# 4G.net
KiCad netlist of a schematic drawn in Altium Designer
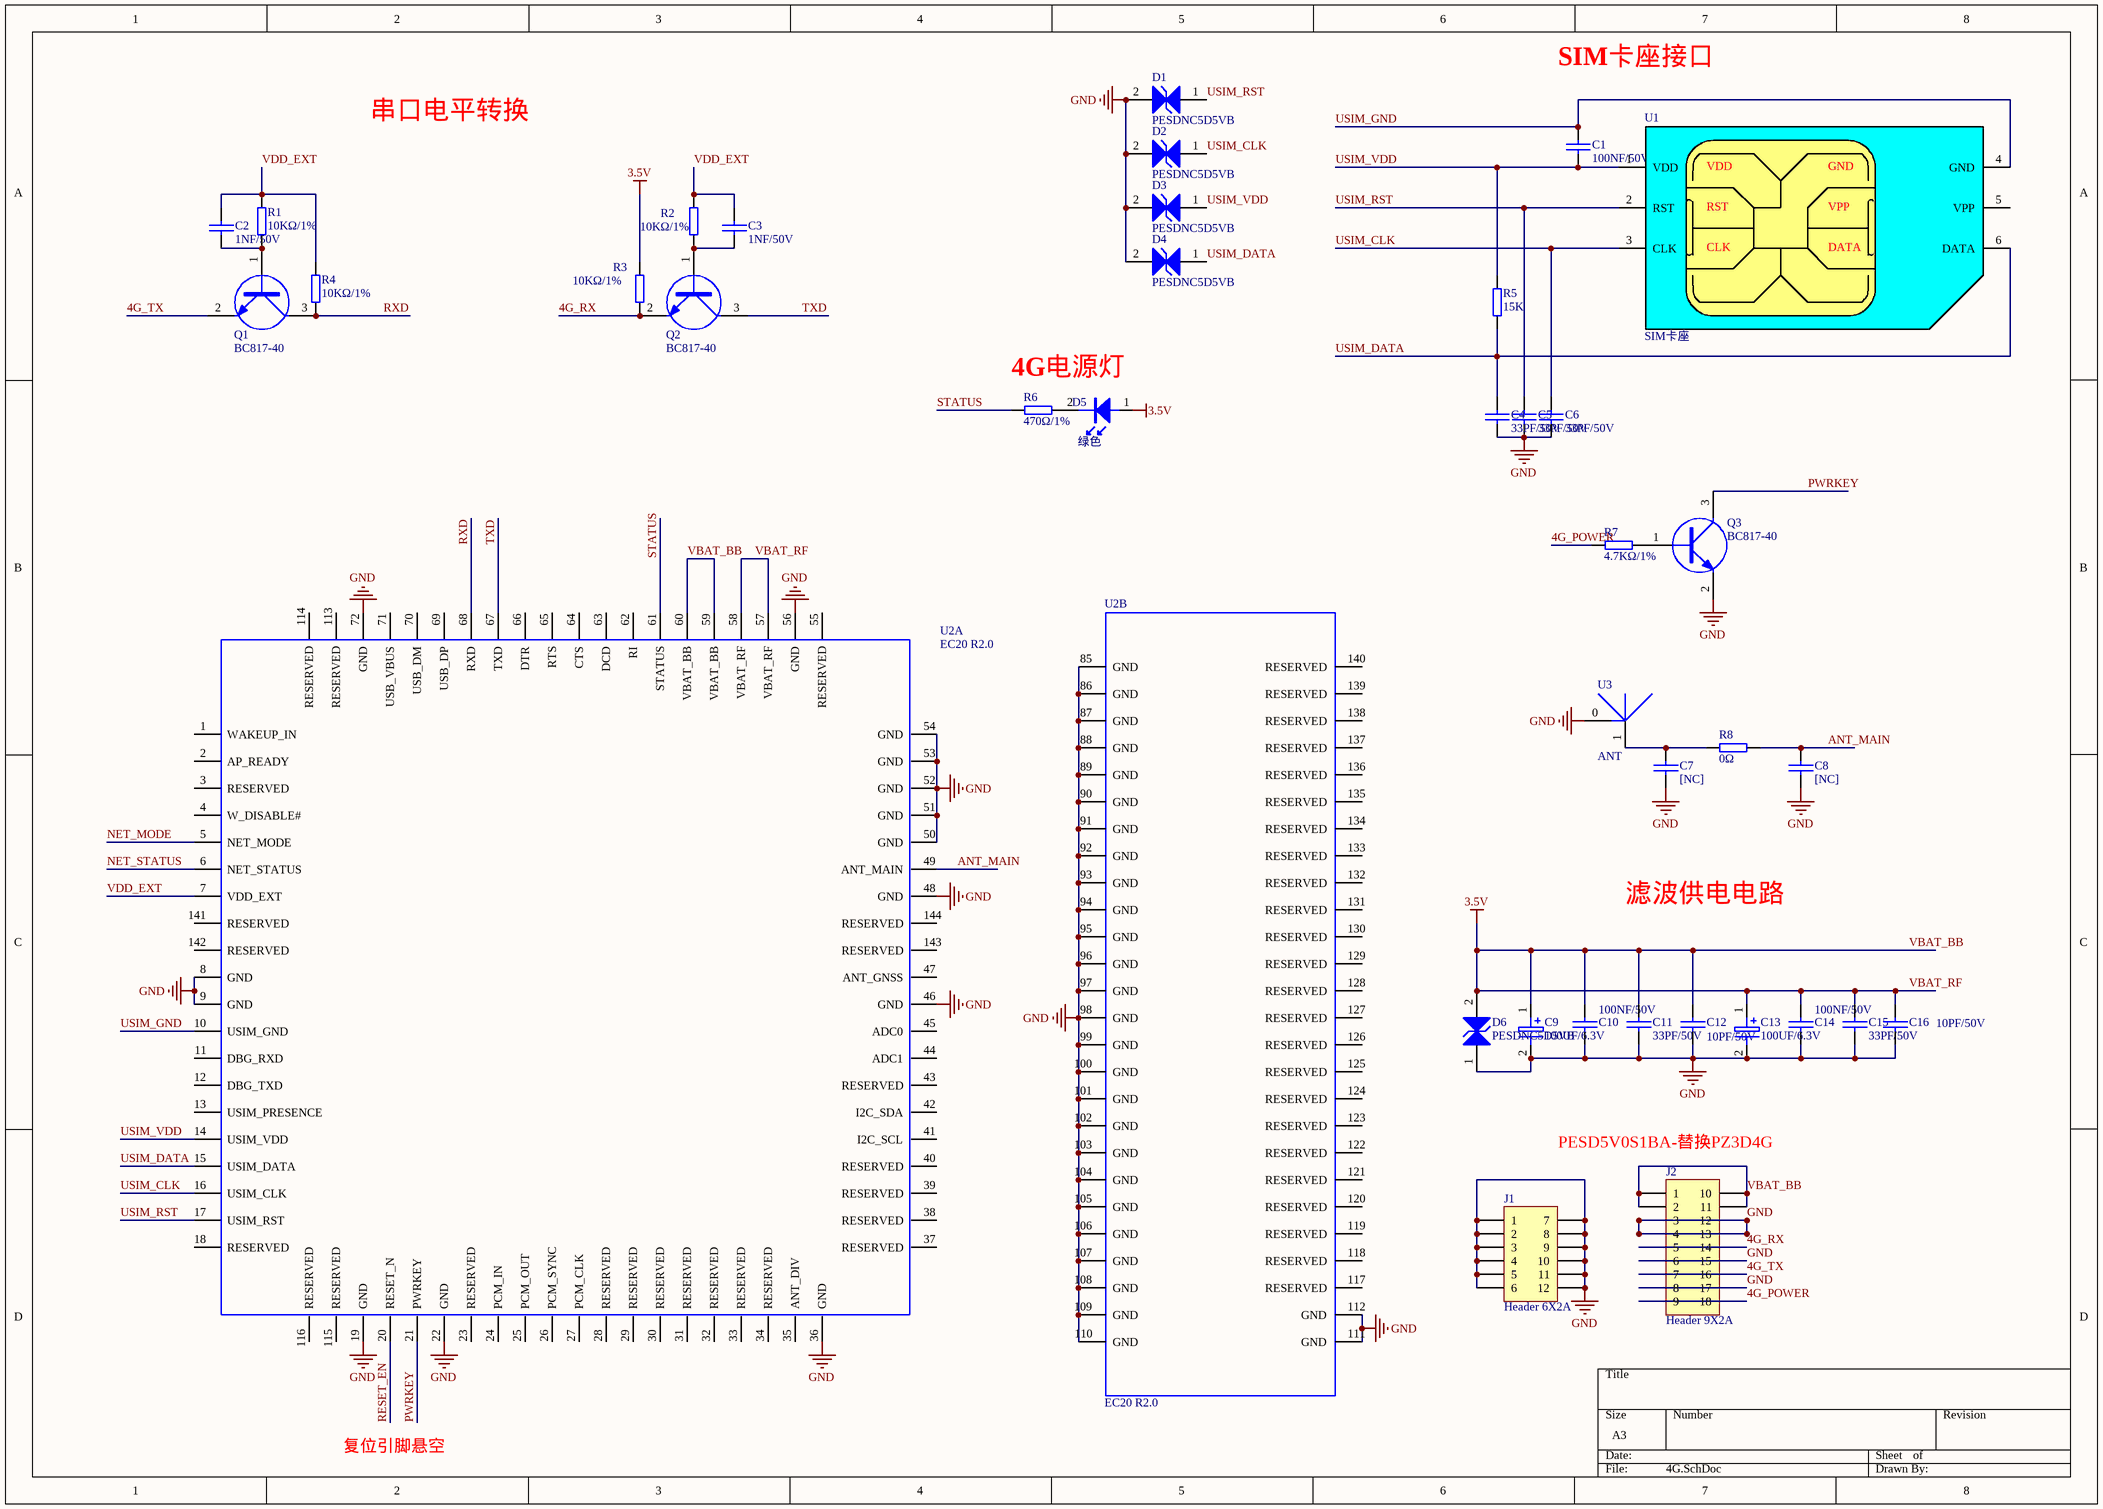
[diagram p0: 4G.SchDoc]

(export (version "E")
  (design (tool "Eeschema 10.0.6"))
  (components
    (comp (ref "C1")
      (value "100NF/50V")
      (footprint "0603_C")
      (description "无极性电容")
      (libsource (lib "Integrated_Library") (part "CAP"))
    )
    (comp (ref "C2")
      (value "1NF/50V")
      (footprint "0603_C")
      (description "无极性电容")
      (libsource (lib "Integrated_Library") (part "CAP"))
    )
    (comp (ref "C3")
      (value "1NF/50V")
      (footprint "0603_C")
      (description "无极性电容")
      (libsource (lib "Integrated_Library") (part "CAP"))
    )
    (comp (ref "C4")
      (value "33PF/50V")
      (footprint "0603_C")
      (description "无极性电容")
      (libsource (lib "Integrated_Library") (part "CAP"))
    )
    (comp (ref "C5")
      (value "33PF/50V")
      (footprint "0603_C")
      (description "无极性电容")
      (libsource (lib "Integrated_Library") (part "CAP"))
    )
    (comp (ref "C6")
      (value "33PF/50V")
      (footprint "0603_C")
      (description "无极性电容")
      (libsource (lib "Integrated_Library") (part "CAP"))
    )
    (comp (ref "C7")
      (value "[NC]")
      (footprint "0603_C")
      (description "无极性电容")
      (libsource (lib "Integrated_Library") (part "CAP"))
    )
    (comp (ref "C8")
      (value "[NC]")
      (footprint "0603_C")
      (description "无极性电容")
      (libsource (lib "Integrated_Library") (part "CAP"))
    )
    (comp (ref "C9")
      (value "100UF/6.3V")
      (footprint "CASE-B_3528")
      (description "钽电容")
      (libsource (lib "Integrated_Library") (part "CAP POLAR"))
    )
    (comp (ref "C10")
      (value "100NF/50V")
      (footprint "0603_C")
      (description "无极性电容")
      (libsource (lib "Integrated_Library") (part "CAP"))
    )
    (comp (ref "C11")
      (value "33PF/50V")
      (footprint "0603_C")
      (description "无极性电容")
      (libsource (lib "Integrated_Library") (part "CAP"))
    )
    (comp (ref "C12")
      (value "10PF/50V")
      (footprint "0603_C")
      (description "无极性电容")
      (libsource (lib "Integrated_Library") (part "CAP"))
    )
    (comp (ref "C13")
      (value "100UF/6.3V")
      (footprint "CASE-B_3528")
      (description "钽电容")
      (libsource (lib "Integrated_Library") (part "CAP POLAR"))
    )
    (comp (ref "C14")
      (value "100NF/50V")
      (footprint "0603_C")
      (description "无极性电容")
      (libsource (lib "Integrated_Library") (part "CAP"))
    )
    (comp (ref "C15")
      (value "33PF/50V")
      (footprint "0603_C")
      (description "无极性电容")
      (libsource (lib "Integrated_Library") (part "CAP"))
    )
    (comp (ref "C16")
      (value "10PF/50V")
      (footprint "0603_C")
      (description "无极性电容")
      (libsource (lib "Integrated_Library") (part "CAP"))
    )
    (comp (ref "D1")
      (value "PESDNC5D5VB")
      (footprint "SOD-523")
      (description "TVS 瞬态抑制二极管")
      (fields (field (name "PUBLISHER") "Altium Limited"))
      (libsource (lib "Integrated_Library") (part "TVS"))
    )
    (comp (ref "D2")
      (value "PESDNC5D5VB")
      (footprint "SOD-523")
      (description "TVS 瞬态抑制二极管")
      (fields (field (name "PUBLISHER") "Altium Limited"))
      (libsource (lib "Integrated_Library") (part "TVS"))
    )
    (comp (ref "D3")
      (value "PESDNC5D5VB")
      (footprint "SOD-523")
      (description "TVS 瞬态抑制二极管")
      (fields (field (name "PUBLISHER") "Altium Limited"))
      (libsource (lib "Integrated_Library") (part "TVS"))
    )
    (comp (ref "D4")
      (value "PESDNC5D5VB")
      (footprint "SOD-523")
      (description "TVS 瞬态抑制二极管")
      (fields (field (name "PUBLISHER") "Altium Limited"))
      (libsource (lib "Integrated_Library") (part "TVS"))
    )
    (comp (ref "D5")
      (value "绿色")
      (footprint "0603_D")
      (description "发光二极管")
      (libsource (lib "Integrated_Library") (part "LED"))
    )
    (comp (ref "D6")
      (value "PESDNC5D5VB")
      (footprint "SOD-523")
      (description "TVS 瞬态抑制二极管")
      (fields (field (name "PUBLISHER") "Altium Limited"))
      (libsource (lib "Integrated_Library") (part "TVS"))
    )
    (comp (ref "J1")
      (value "Header 6X2A")
      (footprint "HDR2X6_CEN")
      (description "Header, 6-Pin, Dual row")
      (fields (field (name "PUBLISHER") "Altium Limited"))
      (libsource (lib "Miscellaneous Connectors") (part "Header 6X2A"))
    )
    (comp (ref "J2")
      (value "Header 9X2A")
      (footprint "HDR2X9_CEN")
      (description "Header, 9-Pin, Dual row")
      (fields (field (name "PUBLISHER") "Altium Limited"))
      (libsource (lib "Miscellaneous Connectors") (part "Header 9X2A"))
    )
    (comp (ref "Q1")
      (value "BC817-40")
      (footprint "SOT-23-3")
      (description "NPN")
      (libsource (lib "Integrated_Library") (part "S8050"))
    )
    (comp (ref "Q2")
      (value "BC817-40")
      (footprint "SOT-23-3")
      (description "NPN")
      (libsource (lib "Integrated_Library") (part "S8050"))
    )
    (comp (ref "Q3")
      (value "BC817-40")
      (footprint "SOT-23-3")
      (description "NPN三极管")
      (libsource (lib "Integrated_Library") (part "BC817-40"))
    )
    (comp (ref "R1")
      (value "10KΩ/1%")
      (footprint "0603_R")
      (description "电阻")
      (libsource (lib "Integrated_Library") (part "RES2"))
    )
    (comp (ref "R2")
      (value "10KΩ/1%")
      (footprint "0603_R")
      (description "电阻")
      (libsource (lib "Integrated_Library") (part "RES2"))
    )
    (comp (ref "R3")
      (value "10KΩ/1%")
      (footprint "0603_R")
      (description "电阻")
      (libsource (lib "Integrated_Library") (part "RES2"))
    )
    (comp (ref "R4")
      (value "10KΩ/1%")
      (footprint "0603_R")
      (description "电阻")
      (libsource (lib "Integrated_Library") (part "RES2"))
    )
    (comp (ref "R5")
      (value "15K")
      (footprint "0603_R")
      (description "电阻")
      (libsource (lib "Integrated_Library") (part "RES2"))
    )
    (comp (ref "R6")
      (value "470Ω/1%")
      (footprint "0603_R")
      (description "电阻")
      (libsource (lib "Integrated_Library") (part "RES2"))
    )
    (comp (ref "R7")
      (value "4.7KΩ/1%")
      (footprint "0603_R")
      (description "电阻")
      (libsource (lib "Integrated_Library") (part "RES2"))
    )
    (comp (ref "R8")
      (value "0Ω")
      (footprint "0603_R")
      (description "电阻")
      (libsource (lib "Integrated_Library") (part "RES2"))
    )
    (comp (ref "U1")
      (value "SIM卡座")
      (footprint "SIM卡座-NANO掀盖式")
      (description "无保护引脚SIM卡座")
      (libsource (lib "MyLib Schlib") (part "SIM卡座"))
    )
    (comp (ref "U2")
      (value "EC20 R2.0")
      (footprint "EC20_R2.0")
      (description "移远通信4G")
      (libsource (lib "Integrated_Library") (part "EC20 R2.0"))
    )
    (comp (ref "U3")
      (value "ANT")
      (footprint "SMA-KWE/弯头")
      (description "天线座")
      (libsource (lib "Integrated_Library") (part "ANT"))
    )
  )
  (nets
    (net (code "1") (name "/4G_POWER") (class "Default")
      (node (ref "J2") (pin "18") (pinfunction "18_18") (pintype "passive"))
      (node (ref "J2") (pin "9") (pinfunction "9_9") (pintype "passive"))
      (node (ref "R7") (pin "1") (pinfunction "1_1") (pintype "passive"))
    )
    (net (code "2") (name "/4G_RX") (class "Default")
      (node (ref "J2") (pin "14") (pinfunction "14_14") (pintype "passive"))
      (node (ref "J2") (pin "5") (pinfunction "5_5") (pintype "passive"))
      (node (ref "Q2") (pin "2") (pinfunction "2_2") (pintype "passive"))
      (node (ref "R3") (pin "1") (pinfunction "1_1") (pintype "passive"))
    )
    (net (code "3") (name "/4G_TX") (class "Default")
      (node (ref "J2") (pin "16") (pinfunction "16_16") (pintype "passive"))
      (node (ref "J2") (pin "7") (pinfunction "7_7") (pintype "passive"))
      (node (ref "Q1") (pin "2") (pinfunction "2_2") (pintype "passive"))
    )
    (net (code "4") (name "/ANT_MAIN") (class "Default")
      (node (ref "C8") (pin "1") (pinfunction "1_1") (pintype "passive"))
      (node (ref "R8") (pin "2") (pinfunction "2_2") (pintype "passive"))
      (node (ref "U2") (pin "49") (pinfunction "ANT_MAIN_49") (pintype "passive"))
    )
    (net (code "5") (name "/NET_MODE") (class "Default")
      (node (ref "U2") (pin "5") (pinfunction "NET_MODE_5") (pintype "passive"))
    )
    (net (code "6") (name "/NET_STATUS") (class "Default")
      (node (ref "U2") (pin "6") (pinfunction "NET_STATUS_6") (pintype "passive"))
    )
    (net (code "7") (name "/PWRKEY") (class "Default")
      (node (ref "Q3") (pin "3") (pinfunction "3_3") (pintype "passive"))
      (node (ref "U2") (pin "21") (pinfunction "PWRKEY_21") (pintype "passive"))
    )
    (net (code "8") (name "/RESET_EN") (class "Default")
      (node (ref "U2") (pin "20") (pinfunction "RESET_N_20") (pintype "passive"))
    )
    (net (code "9") (name "/RXD") (class "Default")
      (node (ref "Q1") (pin "3") (pinfunction "3_3") (pintype "passive"))
      (node (ref "R4") (pin "1") (pinfunction "1_1") (pintype "passive"))
      (node (ref "U2") (pin "68") (pinfunction "RXD_68") (pintype "passive"))
    )
    (net (code "10") (name "/STATUS") (class "Default")
      (node (ref "R6") (pin "1") (pinfunction "1_1") (pintype "passive"))
      (node (ref "U2") (pin "61") (pinfunction "STATUS_61") (pintype "passive"))
    )
    (net (code "11") (name "/TXD") (class "Default")
      (node (ref "Q2") (pin "3") (pinfunction "3_3") (pintype "passive"))
      (node (ref "U2") (pin "67") (pinfunction "TXD_67") (pintype "passive"))
    )
    (net (code "12") (name "/USIM_CLK") (class "Default")
      (node (ref "C6") (pin "1") (pinfunction "1_1") (pintype "passive"))
      (node (ref "D2") (pin "1") (pinfunction "1_1") (pintype "passive"))
      (node (ref "U1") (pin "3") (pinfunction "CLK_3") (pintype "passive"))
      (node (ref "U2") (pin "16") (pinfunction "USIM_CLK_16") (pintype "passive"))
    )
    (net (code "13") (name "/USIM_DATA") (class "Default")
      (node (ref "C4") (pin "1") (pinfunction "1_1") (pintype "passive"))
      (node (ref "D4") (pin "1") (pinfunction "1_1") (pintype "passive"))
      (node (ref "R5") (pin "1") (pinfunction "1_1") (pintype "passive"))
      (node (ref "U1") (pin "6") (pinfunction "DATA_6") (pintype "passive"))
      (node (ref "U2") (pin "15") (pinfunction "USIM_DATA_15") (pintype "passive"))
    )
    (net (code "14") (name "/USIM_GND") (class "Default")
      (node (ref "C1") (pin "1") (pinfunction "1_1") (pintype "passive"))
      (node (ref "U1") (pin "4") (pinfunction "GND_4") (pintype "passive"))
      (node (ref "U2") (pin "10") (pinfunction "USIM_GND_10") (pintype "passive"))
    )
    (net (code "15") (name "/USIM_RST") (class "Default")
      (node (ref "C5") (pin "1") (pinfunction "1_1") (pintype "passive"))
      (node (ref "D1") (pin "1") (pinfunction "1_1") (pintype "passive"))
      (node (ref "U1") (pin "2") (pinfunction "RST_2") (pintype "passive"))
      (node (ref "U2") (pin "17") (pinfunction "USIM_RST_17") (pintype "passive"))
    )
    (net (code "16") (name "/USIM_VDD") (class "Default")
      (node (ref "C1") (pin "2") (pinfunction "2_2") (pintype "passive"))
      (node (ref "D3") (pin "1") (pinfunction "1_1") (pintype "passive"))
      (node (ref "R5") (pin "2") (pinfunction "2_2") (pintype "passive"))
      (node (ref "U1") (pin "1") (pinfunction "VDD_1") (pintype "passive"))
      (node (ref "U2") (pin "14") (pinfunction "USIM_VDD_14") (pintype "passive"))
    )
    (net (code "17") (name "/VDD_EXT") (class "Default")
      (node (ref "C2") (pin "1") (pinfunction "1_1") (pintype "passive"))
      (node (ref "C3") (pin "1") (pinfunction "1_1") (pintype "passive"))
      (node (ref "R1") (pin "2") (pinfunction "2_2") (pintype "passive"))
      (node (ref "R2") (pin "2") (pinfunction "2_2") (pintype "passive"))
      (node (ref "R4") (pin "2") (pinfunction "2_2") (pintype "passive"))
      (node (ref "U2") (pin "7") (pinfunction "VDD_EXT_7") (pintype "passive"))
    )
    (net (code "18") (name "3.5V") (class "Default")
      (node (ref "C10") (pin "1") (pinfunction "1_1") (pintype "passive"))
      (node (ref "C11") (pin "1") (pinfunction "1_1") (pintype "passive"))
      (node (ref "C12") (pin "1") (pinfunction "1_1") (pintype "passive"))
      (node (ref "C13") (pin "1") (pinfunction "1_1") (pintype "passive"))
      (node (ref "C14") (pin "1") (pinfunction "1_1") (pintype "passive"))
      (node (ref "C15") (pin "1") (pinfunction "1_1") (pintype "passive"))
      (node (ref "C16") (pin "1") (pinfunction "1_1") (pintype "passive"))
      (node (ref "C9") (pin "1") (pinfunction "1_1") (pintype "passive"))
      (node (ref "D5") (pin "1") (pinfunction "1_1") (pintype "passive"))
      (node (ref "D6") (pin "2") (pinfunction "K_2") (pintype "passive"))
      (node (ref "J2") (pin "1") (pinfunction "1_1") (pintype "passive"))
      (node (ref "J2") (pin "10") (pinfunction "10_10") (pintype "passive"))
      (node (ref "J2") (pin "11") (pinfunction "11_11") (pintype "passive"))
      (node (ref "J2") (pin "2") (pinfunction "2_2") (pintype "passive"))
      (node (ref "R3") (pin "2") (pinfunction "2_2") (pintype "passive"))
      (node (ref "U2") (pin "57") (pinfunction "VBAT_RF_57") (pintype "passive"))
      (node (ref "U2") (pin "58") (pinfunction "VBAT_RF_58") (pintype "passive"))
      (node (ref "U2") (pin "59") (pinfunction "VBAT_BB_59") (pintype "passive"))
      (node (ref "U2") (pin "60") (pinfunction "VBAT_BB_60") (pintype "passive"))
    )
    (net (code "19") (name "GND") (class "Default")
      (node (ref "C10") (pin "2") (pinfunction "2_2") (pintype "passive"))
      (node (ref "C11") (pin "2") (pinfunction "2_2") (pintype "passive"))
      (node (ref "C12") (pin "2") (pinfunction "2_2") (pintype "passive"))
      (node (ref "C13") (pin "2") (pinfunction "2_2") (pintype "passive"))
      (node (ref "C14") (pin "2") (pinfunction "2_2") (pintype "passive"))
      (node (ref "C15") (pin "2") (pinfunction "2_2") (pintype "passive"))
      (node (ref "C16") (pin "2") (pinfunction "2_2") (pintype "passive"))
      (node (ref "C4") (pin "2") (pinfunction "2_2") (pintype "passive"))
      (node (ref "C5") (pin "2") (pinfunction "2_2") (pintype "passive"))
      (node (ref "C6") (pin "2") (pinfunction "2_2") (pintype "passive"))
      (node (ref "C7") (pin "2") (pinfunction "2_2") (pintype "passive"))
      (node (ref "C8") (pin "2") (pinfunction "2_2") (pintype "passive"))
      (node (ref "C9") (pin "2") (pinfunction "2_2") (pintype "passive"))
      (node (ref "D1") (pin "2") (pinfunction "K_2") (pintype "passive"))
      (node (ref "D2") (pin "2") (pinfunction "K_2") (pintype "passive"))
      (node (ref "D3") (pin "2") (pinfunction "K_2") (pintype "passive"))
      (node (ref "D4") (pin "2") (pinfunction "K_2") (pintype "passive"))
      (node (ref "D6") (pin "1") (pinfunction "1_1") (pintype "passive"))
      (node (ref "J1") (pin "1") (pinfunction "1_1") (pintype "passive"))
      (node (ref "J1") (pin "10") (pinfunction "10_10") (pintype "passive"))
      (node (ref "J1") (pin "11") (pinfunction "11_11") (pintype "passive"))
      (node (ref "J1") (pin "12") (pinfunction "12_12") (pintype "passive"))
      (node (ref "J1") (pin "2") (pinfunction "2_2") (pintype "passive"))
      (node (ref "J1") (pin "3") (pinfunction "3_3") (pintype "passive"))
      (node (ref "J1") (pin "4") (pinfunction "4_4") (pintype "passive"))
      (node (ref "J1") (pin "5") (pinfunction "5_5") (pintype "passive"))
      (node (ref "J1") (pin "6") (pinfunction "6_6") (pintype "passive"))
      (node (ref "J1") (pin "7") (pinfunction "7_7") (pintype "passive"))
      (node (ref "J1") (pin "8") (pinfunction "8_8") (pintype "passive"))
      (node (ref "J1") (pin "9") (pinfunction "9_9") (pintype "passive"))
      (node (ref "J2") (pin "12") (pinfunction "12_12") (pintype "passive"))
      (node (ref "J2") (pin "13") (pinfunction "13_13") (pintype "passive"))
      (node (ref "J2") (pin "15") (pinfunction "15_15") (pintype "passive"))
      (node (ref "J2") (pin "17") (pinfunction "17_17") (pintype "passive"))
      (node (ref "J2") (pin "3") (pinfunction "3_3") (pintype "passive"))
      (node (ref "J2") (pin "4") (pinfunction "4_4") (pintype "passive"))
      (node (ref "J2") (pin "6") (pinfunction "6_6") (pintype "passive"))
      (node (ref "J2") (pin "8") (pinfunction "8_8") (pintype "passive"))
      (node (ref "Q3") (pin "2") (pinfunction "2_2") (pintype "passive"))
      (node (ref "U2") (pin "100") (pinfunction "GND_100") (pintype "passive"))
      (node (ref "U2") (pin "101") (pinfunction "GND_101") (pintype "passive"))
      (node (ref "U2") (pin "102") (pinfunction "GND_102") (pintype "passive"))
      (node (ref "U2") (pin "103") (pinfunction "GND_103") (pintype "passive"))
      (node (ref "U2") (pin "104") (pinfunction "GND_104") (pintype "passive"))
      (node (ref "U2") (pin "105") (pinfunction "GND_105") (pintype "passive"))
      (node (ref "U2") (pin "106") (pinfunction "GND_106") (pintype "passive"))
      (node (ref "U2") (pin "107") (pinfunction "GND_107") (pintype "passive"))
      (node (ref "U2") (pin "108") (pinfunction "GND_108") (pintype "passive"))
      (node (ref "U2") (pin "109") (pinfunction "GND_109") (pintype "passive"))
      (node (ref "U2") (pin "110") (pinfunction "GND_110") (pintype "passive"))
      (node (ref "U2") (pin "111") (pinfunction "GND_111") (pintype "passive"))
      (node (ref "U2") (pin "112") (pinfunction "GND_112") (pintype "passive"))
      (node (ref "U2") (pin "19") (pinfunction "GND_19") (pintype "passive"))
      (node (ref "U2") (pin "22") (pinfunction "GND_22") (pintype "passive"))
      (node (ref "U2") (pin "36") (pinfunction "GND_36") (pintype "passive"))
      (node (ref "U2") (pin "46") (pinfunction "GND_46") (pintype "passive"))
      (node (ref "U2") (pin "48") (pinfunction "GND_48") (pintype "passive"))
      (node (ref "U2") (pin "50") (pinfunction "GND_50") (pintype "passive"))
      (node (ref "U2") (pin "51") (pinfunction "GND_51") (pintype "passive"))
      (node (ref "U2") (pin "52") (pinfunction "GND_52") (pintype "passive"))
      (node (ref "U2") (pin "53") (pinfunction "GND_53") (pintype "passive"))
      (node (ref "U2") (pin "54") (pinfunction "GND_54") (pintype "passive"))
      (node (ref "U2") (pin "56") (pinfunction "GND_56") (pintype "passive"))
      (node (ref "U2") (pin "72") (pinfunction "GND_72") (pintype "passive"))
      (node (ref "U2") (pin "8") (pinfunction "GND_8") (pintype "passive"))
      (node (ref "U2") (pin "85") (pinfunction "GND_85") (pintype "passive"))
      (node (ref "U2") (pin "86") (pinfunction "GND_86") (pintype "passive"))
      (node (ref "U2") (pin "87") (pinfunction "GND_87") (pintype "passive"))
      (node (ref "U2") (pin "88") (pinfunction "GND_88") (pintype "passive"))
      (node (ref "U2") (pin "89") (pinfunction "GND_89") (pintype "passive"))
      (node (ref "U2") (pin "9") (pinfunction "GND_9") (pintype "passive"))
      (node (ref "U2") (pin "90") (pinfunction "GND_90") (pintype "passive"))
      (node (ref "U2") (pin "91") (pinfunction "GND_91") (pintype "passive"))
      (node (ref "U2") (pin "92") (pinfunction "GND_92") (pintype "passive"))
      (node (ref "U2") (pin "93") (pinfunction "GND_93") (pintype "passive"))
      (node (ref "U2") (pin "94") (pinfunction "GND_94") (pintype "passive"))
      (node (ref "U2") (pin "95") (pinfunction "GND_95") (pintype "passive"))
      (node (ref "U2") (pin "96") (pinfunction "GND_96") (pintype "passive"))
      (node (ref "U2") (pin "97") (pinfunction "GND_97") (pintype "passive"))
      (node (ref "U2") (pin "98") (pinfunction "GND_98") (pintype "passive"))
      (node (ref "U2") (pin "99") (pinfunction "GND_99") (pintype "passive"))
      (node (ref "U3") (pin "0") (pinfunction "0_0") (pintype "passive"))
    )
    (net (code "20") (name "Net-(C2-Pad2)") (class "Default")
      (node (ref "C2") (pin "2") (pinfunction "2_2") (pintype "passive"))
      (node (ref "Q1") (pin "1") (pinfunction "1_1") (pintype "passive"))
      (node (ref "R1") (pin "1") (pinfunction "1_1") (pintype "passive"))
    )
    (net (code "21") (name "Net-(C3-Pad2)") (class "Default")
      (node (ref "C3") (pin "2") (pinfunction "2_2") (pintype "passive"))
      (node (ref "Q2") (pin "1") (pinfunction "1_1") (pintype "passive"))
      (node (ref "R2") (pin "1") (pinfunction "1_1") (pintype "passive"))
    )
    (net (code "22") (name "Net-(C7-Pad1)") (class "Default")
      (node (ref "C7") (pin "1") (pinfunction "1_1") (pintype "passive"))
      (node (ref "R8") (pin "1") (pinfunction "1_1") (pintype "passive"))
      (node (ref "U3") (pin "1") (pinfunction "1_1") (pintype "passive"))
    )
    (net (code "23") (name "Net-(D5-Pad2)") (class "Default")
      (node (ref "D5") (pin "2") (pinfunction "2_2") (pintype "passive"))
      (node (ref "R6") (pin "2") (pinfunction "2_2") (pintype "passive"))
    )
    (net (code "24") (name "Net-(Q3-Pad1)") (class "Default")
      (node (ref "Q3") (pin "1") (pinfunction "1_1") (pintype "passive"))
      (node (ref "R7") (pin "2") (pinfunction "2_2") (pintype "passive"))
    )
    (net (code "25") (name "unconnected-(U1-VPP-Pad5)") (class "Default")
      (node (ref "U1") (pin "5") (pinfunction "VPP_5") (pintype "passive"))
    )
    (net (code "26") (name "unconnected-(U2A-ADC0-Pad45)") (class "Default")
      (node (ref "U2") (pin "45") (pinfunction "ADC0_45") (pintype "passive"))
    )
    (net (code "27") (name "unconnected-(U2A-ADC1-Pad44)") (class "Default")
      (node (ref "U2") (pin "44") (pinfunction "ADC1_44") (pintype "passive"))
    )
    (net (code "28") (name "unconnected-(U2A-ANT_DIV-Pad35)") (class "Default")
      (node (ref "U2") (pin "35") (pinfunction "ANT_DIV_35") (pintype "passive"))
    )
    (net (code "29") (name "unconnected-(U2A-ANT_GNSS-Pad47)") (class "Default")
      (node (ref "U2") (pin "47") (pinfunction "ANT_GNSS_47") (pintype "passive"))
    )
    (net (code "30") (name "unconnected-(U2A-AP_READY-Pad2)") (class "Default")
      (node (ref "U2") (pin "2") (pinfunction "AP_READY_2") (pintype "passive"))
    )
    (net (code "31") (name "unconnected-(U2A-CTS-Pad64)") (class "Default")
      (node (ref "U2") (pin "64") (pinfunction "CTS_64") (pintype "passive"))
    )
    (net (code "32") (name "unconnected-(U2A-DBG_RXD-Pad11)") (class "Default")
      (node (ref "U2") (pin "11") (pinfunction "DBG_RXD_11") (pintype "passive"))
    )
    (net (code "33") (name "unconnected-(U2A-DBG_TXD-Pad12)") (class "Default")
      (node (ref "U2") (pin "12") (pinfunction "DBG_TXD_12") (pintype "passive"))
    )
    (net (code "34") (name "unconnected-(U2A-DCD-Pad63)") (class "Default")
      (node (ref "U2") (pin "63") (pinfunction "DCD_63") (pintype "passive"))
    )
    (net (code "35") (name "unconnected-(U2A-DTR-Pad66)") (class "Default")
      (node (ref "U2") (pin "66") (pinfunction "DTR_66") (pintype "passive"))
    )
    (net (code "36") (name "unconnected-(U2A-I2C_SCL-Pad41)") (class "Default")
      (node (ref "U2") (pin "41") (pinfunction "I2C_SCL_41") (pintype "passive"))
    )
    (net (code "37") (name "unconnected-(U2A-I2C_SDA-Pad42)") (class "Default")
      (node (ref "U2") (pin "42") (pinfunction "I2C_SDA_42") (pintype "passive"))
    )
    (net (code "38") (name "unconnected-(U2A-PCM_CLK-Pad27)") (class "Default")
      (node (ref "U2") (pin "27") (pinfunction "PCM_CLK_27") (pintype "passive"))
    )
    (net (code "39") (name "unconnected-(U2A-PCM_IN-Pad24)") (class "Default")
      (node (ref "U2") (pin "24") (pinfunction "PCM_IN_24") (pintype "passive"))
    )
    (net (code "40") (name "unconnected-(U2A-PCM_OUT-Pad25)") (class "Default")
      (node (ref "U2") (pin "25") (pinfunction "PCM_OUT_25") (pintype "passive"))
    )
    (net (code "41") (name "unconnected-(U2A-PCM_SYNC-Pad26)") (class "Default")
      (node (ref "U2") (pin "26") (pinfunction "PCM_SYNC_26") (pintype "passive"))
    )
    (net (code "42") (name "unconnected-(U2A-RESERVED-Pad3)") (class "Default")
      (node (ref "U2") (pin "3") (pinfunction "RESERVED_3") (pintype "passive"))
    )
    (net (code "43") (name "unconnected-(U2A-RESERVED-Pad18)") (class "Default")
      (node (ref "U2") (pin "18") (pinfunction "RESERVED_18") (pintype "passive"))
    )
    (net (code "44") (name "unconnected-(U2A-RESERVED-Pad23)") (class "Default")
      (node (ref "U2") (pin "23") (pinfunction "RESERVED_23") (pintype "passive"))
    )
    (net (code "45") (name "unconnected-(U2A-RESERVED-Pad28)") (class "Default")
      (node (ref "U2") (pin "28") (pinfunction "RESERVED_28") (pintype "passive"))
    )
    (net (code "46") (name "unconnected-(U2A-RESERVED-Pad29)") (class "Default")
      (node (ref "U2") (pin "29") (pinfunction "RESERVED_29") (pintype "passive"))
    )
    (net (code "47") (name "unconnected-(U2A-RESERVED-Pad30)") (class "Default")
      (node (ref "U2") (pin "30") (pinfunction "RESERVED_30") (pintype "passive"))
    )
    (net (code "48") (name "unconnected-(U2A-RESERVED-Pad31)") (class "Default")
      (node (ref "U2") (pin "31") (pinfunction "RESERVED_31") (pintype "passive"))
    )
    (net (code "49") (name "unconnected-(U2A-RESERVED-Pad32)") (class "Default")
      (node (ref "U2") (pin "32") (pinfunction "RESERVED_32") (pintype "passive"))
    )
    (net (code "50") (name "unconnected-(U2A-RESERVED-Pad33)") (class "Default")
      (node (ref "U2") (pin "33") (pinfunction "RESERVED_33") (pintype "passive"))
    )
    (net (code "51") (name "unconnected-(U2A-RESERVED-Pad34)") (class "Default")
      (node (ref "U2") (pin "34") (pinfunction "RESERVED_34") (pintype "passive"))
    )
    (net (code "52") (name "unconnected-(U2A-RESERVED-Pad37)") (class "Default")
      (node (ref "U2") (pin "37") (pinfunction "RESERVED_37") (pintype "passive"))
    )
    (net (code "53") (name "unconnected-(U2A-RESERVED-Pad38)") (class "Default")
      (node (ref "U2") (pin "38") (pinfunction "RESERVED_38") (pintype "passive"))
    )
    (net (code "54") (name "unconnected-(U2A-RESERVED-Pad39)") (class "Default")
      (node (ref "U2") (pin "39") (pinfunction "RESERVED_39") (pintype "passive"))
    )
    (net (code "55") (name "unconnected-(U2A-RESERVED-Pad40)") (class "Default")
      (node (ref "U2") (pin "40") (pinfunction "RESERVED_40") (pintype "passive"))
    )
    (net (code "56") (name "unconnected-(U2A-RESERVED-Pad43)") (class "Default")
      (node (ref "U2") (pin "43") (pinfunction "RESERVED_43") (pintype "passive"))
    )
    (net (code "57") (name "unconnected-(U2A-RESERVED-Pad55)") (class "Default")
      (node (ref "U2") (pin "55") (pinfunction "RESERVED_55") (pintype "passive"))
    )
    (net (code "58") (name "unconnected-(U2A-RESERVED-Pad113)") (class "Default")
      (node (ref "U2") (pin "113") (pinfunction "RESERVED_113") (pintype "passive"))
    )
    (net (code "59") (name "unconnected-(U2A-RESERVED-Pad114)") (class "Default")
      (node (ref "U2") (pin "114") (pinfunction "RESERVED_114") (pintype "passive"))
    )
    (net (code "60") (name "unconnected-(U2A-RESERVED-Pad115)") (class "Default")
      (node (ref "U2") (pin "115") (pinfunction "RESERVED_115") (pintype "passive"))
    )
    (net (code "61") (name "unconnected-(U2A-RESERVED-Pad116)") (class "Default")
      (node (ref "U2") (pin "116") (pinfunction "RESERVED_116") (pintype "passive"))
    )
    (net (code "62") (name "unconnected-(U2A-RESERVED-Pad141)") (class "Default")
      (node (ref "U2") (pin "141") (pinfunction "RESERVED_141") (pintype "passive"))
    )
    (net (code "63") (name "unconnected-(U2A-RESERVED-Pad142)") (class "Default")
      (node (ref "U2") (pin "142") (pinfunction "RESERVED_142") (pintype "passive"))
    )
    (net (code "64") (name "unconnected-(U2A-RESERVED-Pad143)") (class "Default")
      (node (ref "U2") (pin "143") (pinfunction "RESERVED_143") (pintype "passive"))
    )
    (net (code "65") (name "unconnected-(U2A-RESERVED-Pad144)") (class "Default")
      (node (ref "U2") (pin "144") (pinfunction "RESERVED_144") (pintype "passive"))
    )
    (net (code "66") (name "unconnected-(U2A-RI-Pad62)") (class "Default")
      (node (ref "U2") (pin "62") (pinfunction "RI_62") (pintype "passive"))
    )
    (net (code "67") (name "unconnected-(U2A-RTS-Pad65)") (class "Default")
      (node (ref "U2") (pin "65") (pinfunction "RTS_65") (pintype "passive"))
    )
    (net (code "68") (name "unconnected-(U2A-USB_DM-Pad70)") (class "Default")
      (node (ref "U2") (pin "70") (pinfunction "USB_DM_70") (pintype "passive"))
    )
    (net (code "69") (name "unconnected-(U2A-USB_DP-Pad69)") (class "Default")
      (node (ref "U2") (pin "69") (pinfunction "USB_DP_69") (pintype "passive"))
    )
    (net (code "70") (name "unconnected-(U2A-USB_VBUS-Pad71)") (class "Default")
      (node (ref "U2") (pin "71") (pinfunction "USB_VBUS_71") (pintype "passive"))
    )
    (net (code "71") (name "unconnected-(U2A-USIM_PRESENCE-Pad13)") (class "Default")
      (node (ref "U2") (pin "13") (pinfunction "USIM_PRESENCE_13") (pintype "passive"))
    )
    (net (code "72") (name "unconnected-(U2A-WAKEUP_IN-Pad1)") (class "Default")
      (node (ref "U2") (pin "1") (pinfunction "WAKEUP_IN_1") (pintype "passive"))
    )
    (net (code "73") (name "unconnected-(U2A-W_DISABLE#-Pad4)") (class "Default")
      (node (ref "U2") (pin "4") (pinfunction "W_DISABLE#_4") (pintype "passive"))
    )
    (net (code "74") (name "unconnected-(U2B-RESERVED-Pad117)") (class "Default")
      (node (ref "U2") (pin "117") (pinfunction "RESERVED_117") (pintype "passive"))
    )
    (net (code "75") (name "unconnected-(U2B-RESERVED-Pad118)") (class "Default")
      (node (ref "U2") (pin "118") (pinfunction "RESERVED_118") (pintype "passive"))
    )
    (net (code "76") (name "unconnected-(U2B-RESERVED-Pad119)") (class "Default")
      (node (ref "U2") (pin "119") (pinfunction "RESERVED_119") (pintype "passive"))
    )
    (net (code "77") (name "unconnected-(U2B-RESERVED-Pad120)") (class "Default")
      (node (ref "U2") (pin "120") (pinfunction "RESERVED_120") (pintype "passive"))
    )
    (net (code "78") (name "unconnected-(U2B-RESERVED-Pad121)") (class "Default")
      (node (ref "U2") (pin "121") (pinfunction "RESERVED_121") (pintype "passive"))
    )
    (net (code "79") (name "unconnected-(U2B-RESERVED-Pad122)") (class "Default")
      (node (ref "U2") (pin "122") (pinfunction "RESERVED_122") (pintype "passive"))
    )
    (net (code "80") (name "unconnected-(U2B-RESERVED-Pad123)") (class "Default")
      (node (ref "U2") (pin "123") (pinfunction "RESERVED_123") (pintype "passive"))
    )
    (net (code "81") (name "unconnected-(U2B-RESERVED-Pad124)") (class "Default")
      (node (ref "U2") (pin "124") (pinfunction "RESERVED_124") (pintype "passive"))
    )
    (net (code "82") (name "unconnected-(U2B-RESERVED-Pad125)") (class "Default")
      (node (ref "U2") (pin "125") (pinfunction "RESERVED_125") (pintype "passive"))
    )
    (net (code "83") (name "unconnected-(U2B-RESERVED-Pad126)") (class "Default")
      (node (ref "U2") (pin "126") (pinfunction "RESERVED_126") (pintype "passive"))
    )
    (net (code "84") (name "unconnected-(U2B-RESERVED-Pad127)") (class "Default")
      (node (ref "U2") (pin "127") (pinfunction "RESERVED_127") (pintype "passive"))
    )
    (net (code "85") (name "unconnected-(U2B-RESERVED-Pad128)") (class "Default")
      (node (ref "U2") (pin "128") (pinfunction "RESERVED_128") (pintype "passive"))
    )
    (net (code "86") (name "unconnected-(U2B-RESERVED-Pad129)") (class "Default")
      (node (ref "U2") (pin "129") (pinfunction "RESERVED_129") (pintype "passive"))
    )
    (net (code "87") (name "unconnected-(U2B-RESERVED-Pad130)") (class "Default")
      (node (ref "U2") (pin "130") (pinfunction "RESERVED_130") (pintype "passive"))
    )
    (net (code "88") (name "unconnected-(U2B-RESERVED-Pad131)") (class "Default")
      (node (ref "U2") (pin "131") (pinfunction "RESERVED_131") (pintype "passive"))
    )
    (net (code "89") (name "unconnected-(U2B-RESERVED-Pad132)") (class "Default")
      (node (ref "U2") (pin "132") (pinfunction "RESERVED_132") (pintype "passive"))
    )
    (net (code "90") (name "unconnected-(U2B-RESERVED-Pad133)") (class "Default")
      (node (ref "U2") (pin "133") (pinfunction "RESERVED_133") (pintype "passive"))
    )
    (net (code "91") (name "unconnected-(U2B-RESERVED-Pad134)") (class "Default")
      (node (ref "U2") (pin "134") (pinfunction "RESERVED_134") (pintype "passive"))
    )
    (net (code "92") (name "unconnected-(U2B-RESERVED-Pad135)") (class "Default")
      (node (ref "U2") (pin "135") (pinfunction "RESERVED_135") (pintype "passive"))
    )
    (net (code "93") (name "unconnected-(U2B-RESERVED-Pad136)") (class "Default")
      (node (ref "U2") (pin "136") (pinfunction "RESERVED_136") (pintype "passive"))
    )
    (net (code "94") (name "unconnected-(U2B-RESERVED-Pad137)") (class "Default")
      (node (ref "U2") (pin "137") (pinfunction "RESERVED_137") (pintype "passive"))
    )
    (net (code "95") (name "unconnected-(U2B-RESERVED-Pad138)") (class "Default")
      (node (ref "U2") (pin "138") (pinfunction "RESERVED_138") (pintype "passive"))
    )
    (net (code "96") (name "unconnected-(U2B-RESERVED-Pad139)") (class "Default")
      (node (ref "U2") (pin "139") (pinfunction "RESERVED_139") (pintype "passive"))
    )
    (net (code "97") (name "unconnected-(U2B-RESERVED-Pad140)") (class "Default")
      (node (ref "U2") (pin "140") (pinfunction "RESERVED_140") (pintype "passive"))
    )
  )
)
